# Teensy4Breakout.net
KiCad netlist of a schematic drawn in EAGLE
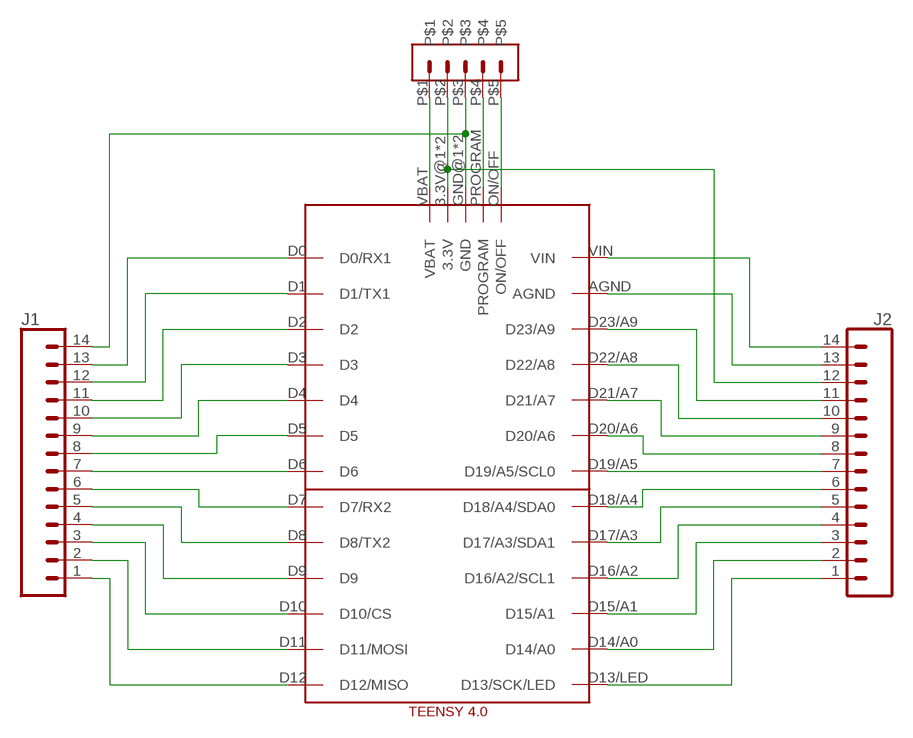
[diagram p0: schematic, sheet 1]

(export (version "E")
  (design (tool "Eeschema 10.0.6"))
  (components
    (comp (ref "J1")
      (value "CONN_14LONGPADS")
      (footprint "eagle-import:1X14-LONGPADS")
      (libsource (lib "eagle-import") (part "CONN_14LONGPADS"))
    )
    (comp (ref "J2")
      (value "CONN_14LONGPADS")
      (footprint "eagle-import:1X14-LONGPADS")
      (libsource (lib "eagle-import") (part "CONN_14LONGPADS"))
    )
    (comp (ref "U$1")
      (value "HEADER1X5")
      (footprint "eagle-import:HEADER1X5")
      (libsource (lib "eagle-import") (part "HEADER1X5"))
    )
    (comp (ref "U$4")
      (value "TEENSY4.0-NOPOGO")
      (footprint "eagle-import:TEENSY4.0-NOPOGO")
      (libsource (lib "eagle-import") (part "TEENSY4.0-NOPOGO"))
    )
  )
  (nets
    (net (code "1") (name "Net-(J1-Pad4)") (class "Default")
      (node (ref "J1") (pin "4") (pinfunction "4_4") (pintype "passive"))
      (node (ref "U$4") (pin "D9") (pinfunction "D9_D9") (pintype "bidirectional"))
    )
    (net (code "2") (name "Net-(J1-Pad7)") (class "Default")
      (node (ref "J1") (pin "7") (pinfunction "7_7") (pintype "passive"))
      (node (ref "U$4") (pin "D6") (pinfunction "D6_D6") (pintype "bidirectional"))
    )
    (net (code "3") (name "Net-(J1-Pad8)") (class "Default")
      (node (ref "J1") (pin "8") (pinfunction "8_8") (pintype "passive"))
      (node (ref "U$4") (pin "D5") (pinfunction "D5_D5") (pintype "bidirectional"))
    )
    (net (code "4") (name "Net-(J1-Pad9)") (class "Default")
      (node (ref "J1") (pin "9") (pinfunction "9_9") (pintype "passive"))
      (node (ref "U$4") (pin "D4") (pinfunction "D4_D4") (pintype "bidirectional"))
    )
    (net (code "5") (name "Net-(J1-Pad10)") (class "Default")
      (node (ref "J1") (pin "10") (pinfunction "10_10") (pintype "passive"))
      (node (ref "U$4") (pin "D3") (pinfunction "D3_D3") (pintype "bidirectional"))
    )
    (net (code "6") (name "Net-(J1-Pad11)") (class "Default")
      (node (ref "J1") (pin "11") (pinfunction "11_11") (pintype "passive"))
      (node (ref "U$4") (pin "D2") (pinfunction "D2_D2") (pintype "bidirectional"))
    )
    (net (code "7") (name "Net-(J1-Pad14)") (class "Default")
      (node (ref "J1") (pin "14") (pinfunction "14_14") (pintype "passive"))
      (node (ref "U$1") (pin "P$3") (pinfunction "P$3_P$3") (pintype "bidirectional"))
      (node (ref "U$4") (pin "GND@1") (pinfunction "GND_GND@1") (pintype "bidirectional"))
      (node (ref "U$4") (pin "GND@2") (pinfunction "GND_GND@2") (pintype "bidirectional"))
    )
    (net (code "8") (name "Net-(J2-Pad2)") (class "Default")
      (node (ref "J2") (pin "2") (pinfunction "2_2") (pintype "passive"))
      (node (ref "U$4") (pin "D14/A0") (pinfunction "D14/A0_D14/A0") (pintype "bidirectional"))
    )
    (net (code "9") (name "Net-(J2-Pad3)") (class "Default")
      (node (ref "J2") (pin "3") (pinfunction "3_3") (pintype "passive"))
      (node (ref "U$4") (pin "D15/A1") (pinfunction "D15/A1_D15/A1") (pintype "bidirectional"))
    )
    (net (code "10") (name "Net-(J2-Pad8)") (class "Default")
      (node (ref "J2") (pin "8") (pinfunction "8_8") (pintype "passive"))
      (node (ref "U$4") (pin "D20/A6") (pinfunction "D20/A6_D20/A6") (pintype "bidirectional"))
    )
    (net (code "11") (name "Net-(J2-Pad9)") (class "Default")
      (node (ref "J2") (pin "9") (pinfunction "9_9") (pintype "passive"))
      (node (ref "U$4") (pin "D21/A7") (pinfunction "D21/A7_D21/A7") (pintype "bidirectional"))
    )
    (net (code "12") (name "Net-(J2-Pad10)") (class "Default")
      (node (ref "J2") (pin "10") (pinfunction "10_10") (pintype "passive"))
      (node (ref "U$4") (pin "D22/A8") (pinfunction "D22/A8_D22/A8") (pintype "bidirectional"))
    )
    (net (code "13") (name "Net-(J2-Pad11)") (class "Default")
      (node (ref "J2") (pin "11") (pinfunction "11_11") (pintype "passive"))
      (node (ref "U$4") (pin "D23/A9") (pinfunction "D23/A9_D23/A9") (pintype "bidirectional"))
    )
    (net (code "14") (name "Net-(J2-Pad12)") (class "Default")
      (node (ref "J2") (pin "12") (pinfunction "12_12") (pintype "passive"))
      (node (ref "U$1") (pin "P$2") (pinfunction "P$2_P$2") (pintype "bidirectional"))
      (node (ref "U$4") (pin "3.3V@1") (pinfunction "3.3V_3.3V@1") (pintype "bidirectional"))
      (node (ref "U$4") (pin "3.3V@2") (pinfunction "3.3V_3.3V@2") (pintype "bidirectional"))
    )
    (net (code "15") (name "Net-(J2-Pad13)") (class "Default")
      (node (ref "J2") (pin "13") (pinfunction "13_13") (pintype "passive"))
      (node (ref "U$4") (pin "AGND") (pinfunction "AGND_AGND") (pintype "bidirectional"))
    )
    (net (code "16") (name "Net-(J2-Pad14)") (class "Default")
      (node (ref "J2") (pin "14") (pinfunction "14_14") (pintype "passive"))
      (node (ref "U$4") (pin "VIN") (pinfunction "VIN_VIN") (pintype "bidirectional"))
    )
    (net (code "17") (name "Net-(U$1-PadP$1)") (class "Default")
      (node (ref "U$1") (pin "P$1") (pinfunction "P$1_P$1") (pintype "bidirectional"))
      (node (ref "U$4") (pin "VBAT") (pinfunction "VBAT_VBAT") (pintype "bidirectional"))
    )
    (net (code "18") (name "Net-(U$1-PadP$4)") (class "Default")
      (node (ref "U$1") (pin "P$4") (pinfunction "P$4_P$4") (pintype "bidirectional"))
      (node (ref "U$4") (pin "PROGRAM") (pinfunction "PROGRAM_PROGRAM") (pintype "bidirectional"))
    )
    (net (code "19") (name "Net-(U$1-PadP$5)") (class "Default")
      (node (ref "U$1") (pin "P$5") (pinfunction "P$5_P$5") (pintype "bidirectional"))
      (node (ref "U$4") (pin "ON/OFF") (pinfunction "ON/OFF_ON/OFF") (pintype "bidirectional"))
    )
    (net (code "20") (name "Net-(U$4-D0{slash}RX1)") (class "Default")
      (node (ref "J1") (pin "13") (pinfunction "13_13") (pintype "passive"))
      (node (ref "U$4") (pin "D0") (pinfunction "D0/RX1_D0") (pintype "bidirectional"))
    )
    (net (code "21") (name "Net-(U$4-D1{slash}TX1)") (class "Default")
      (node (ref "J1") (pin "12") (pinfunction "12_12") (pintype "passive"))
      (node (ref "U$4") (pin "D1") (pinfunction "D1/TX1_D1") (pintype "bidirectional"))
    )
    (net (code "22") (name "Net-(U$4-D7{slash}RX2)") (class "Default")
      (node (ref "J1") (pin "6") (pinfunction "6_6") (pintype "passive"))
      (node (ref "U$4") (pin "D7") (pinfunction "D7/RX2_D7") (pintype "bidirectional"))
    )
    (net (code "23") (name "Net-(U$4-D8{slash}TX2)") (class "Default")
      (node (ref "J1") (pin "5") (pinfunction "5_5") (pintype "passive"))
      (node (ref "U$4") (pin "D8") (pinfunction "D8/TX2_D8") (pintype "bidirectional"))
    )
    (net (code "24") (name "Net-(U$4-D10{slash}CS)") (class "Default")
      (node (ref "J1") (pin "3") (pinfunction "3_3") (pintype "passive"))
      (node (ref "U$4") (pin "D10") (pinfunction "D10/CS_D10") (pintype "bidirectional"))
    )
    (net (code "25") (name "Net-(U$4-D11{slash}MOSI)") (class "Default")
      (node (ref "J1") (pin "2") (pinfunction "2_2") (pintype "passive"))
      (node (ref "U$4") (pin "D11") (pinfunction "D11/MOSI_D11") (pintype "bidirectional"))
    )
    (net (code "26") (name "Net-(U$4-D12{slash}MISO)") (class "Default")
      (node (ref "J1") (pin "1") (pinfunction "1_1") (pintype "passive"))
      (node (ref "U$4") (pin "D12") (pinfunction "D12/MISO_D12") (pintype "bidirectional"))
    )
    (net (code "27") (name "Net-(U$4-D13{slash}SCK{slash}LED)") (class "Default")
      (node (ref "J2") (pin "1") (pinfunction "1_1") (pintype "passive"))
      (node (ref "U$4") (pin "D13/LED") (pinfunction "D13/SCK/LED_D13/LED") (pintype "bidirectional"))
    )
    (net (code "28") (name "Net-(U$4-D16{slash}A2{slash}SCL1)") (class "Default")
      (node (ref "J2") (pin "4") (pinfunction "4_4") (pintype "passive"))
      (node (ref "U$4") (pin "D16/A2") (pinfunction "D16/A2/SCL1_D16/A2") (pintype "bidirectional"))
    )
    (net (code "29") (name "Net-(U$4-D17{slash}A3{slash}SDA1)") (class "Default")
      (node (ref "J2") (pin "5") (pinfunction "5_5") (pintype "passive"))
      (node (ref "U$4") (pin "D17/A3") (pinfunction "D17/A3/SDA1_D17/A3") (pintype "bidirectional"))
    )
    (net (code "30") (name "Net-(U$4-D18{slash}A4{slash}SDA0)") (class "Default")
      (node (ref "J2") (pin "6") (pinfunction "6_6") (pintype "passive"))
      (node (ref "U$4") (pin "D18/A4") (pinfunction "D18/A4/SDA0_D18/A4") (pintype "bidirectional"))
    )
    (net (code "31") (name "Net-(U$4-D19{slash}A5{slash}SCL0)") (class "Default")
      (node (ref "J2") (pin "7") (pinfunction "7_7") (pintype "passive"))
      (node (ref "U$4") (pin "D19/A5") (pinfunction "D19/A5/SCL0_D19/A5") (pintype "bidirectional"))
    )
  )
)
